# MicroPlayerSCH.net
KiCad netlist of a schematic drawn in Altium Designer
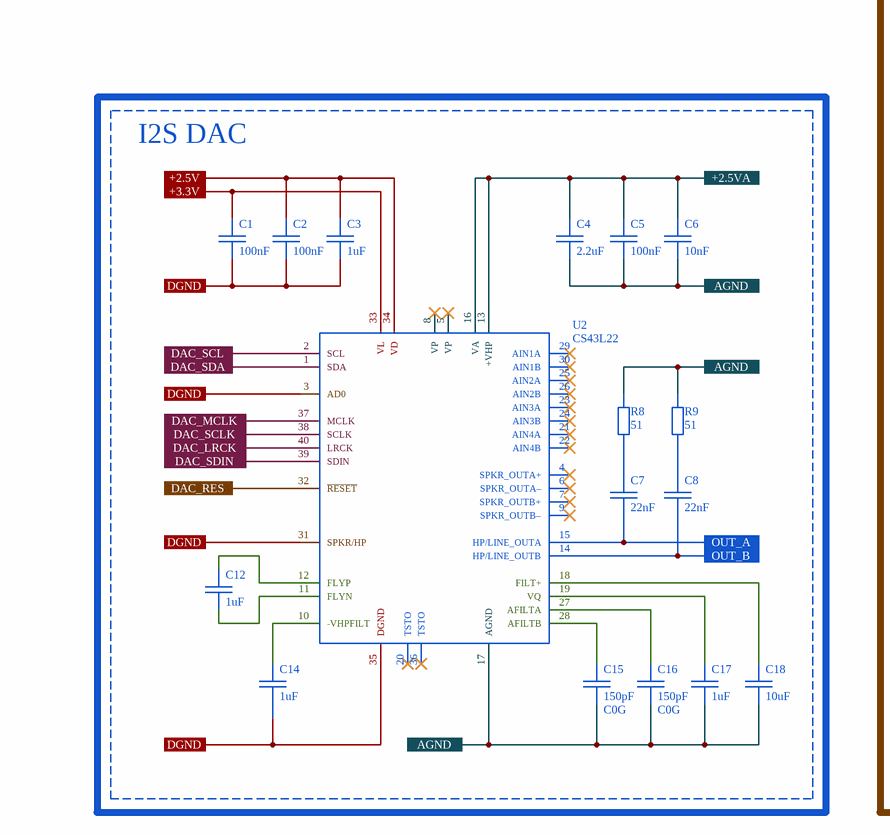
[diagram p0: MicroPlayerSCH.SchDoc, top left]
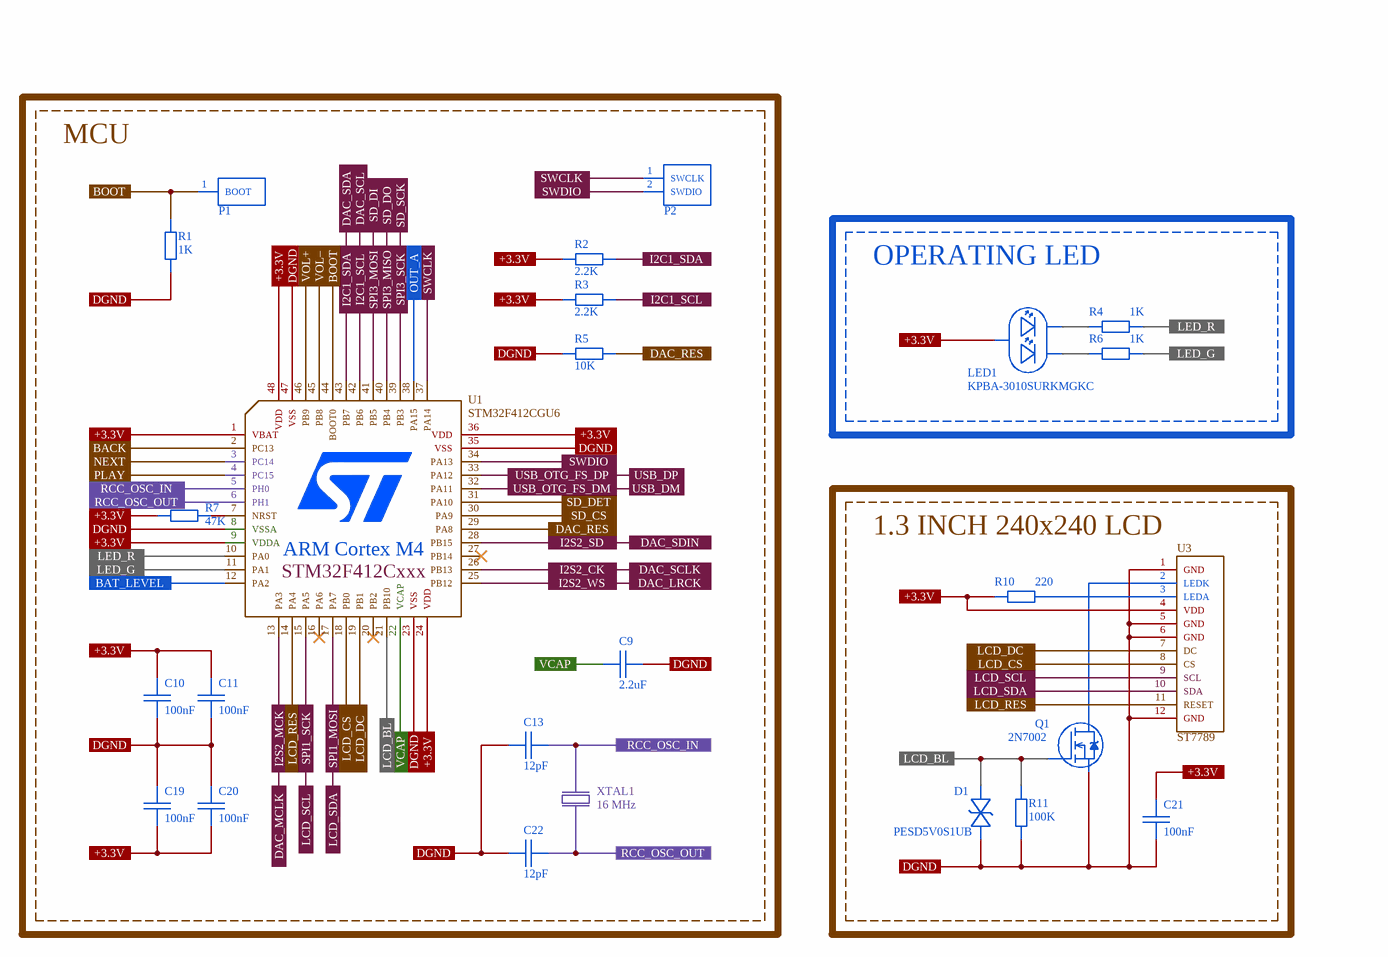
[diagram p1: MicroPlayerSCH.SchDoc, top right]
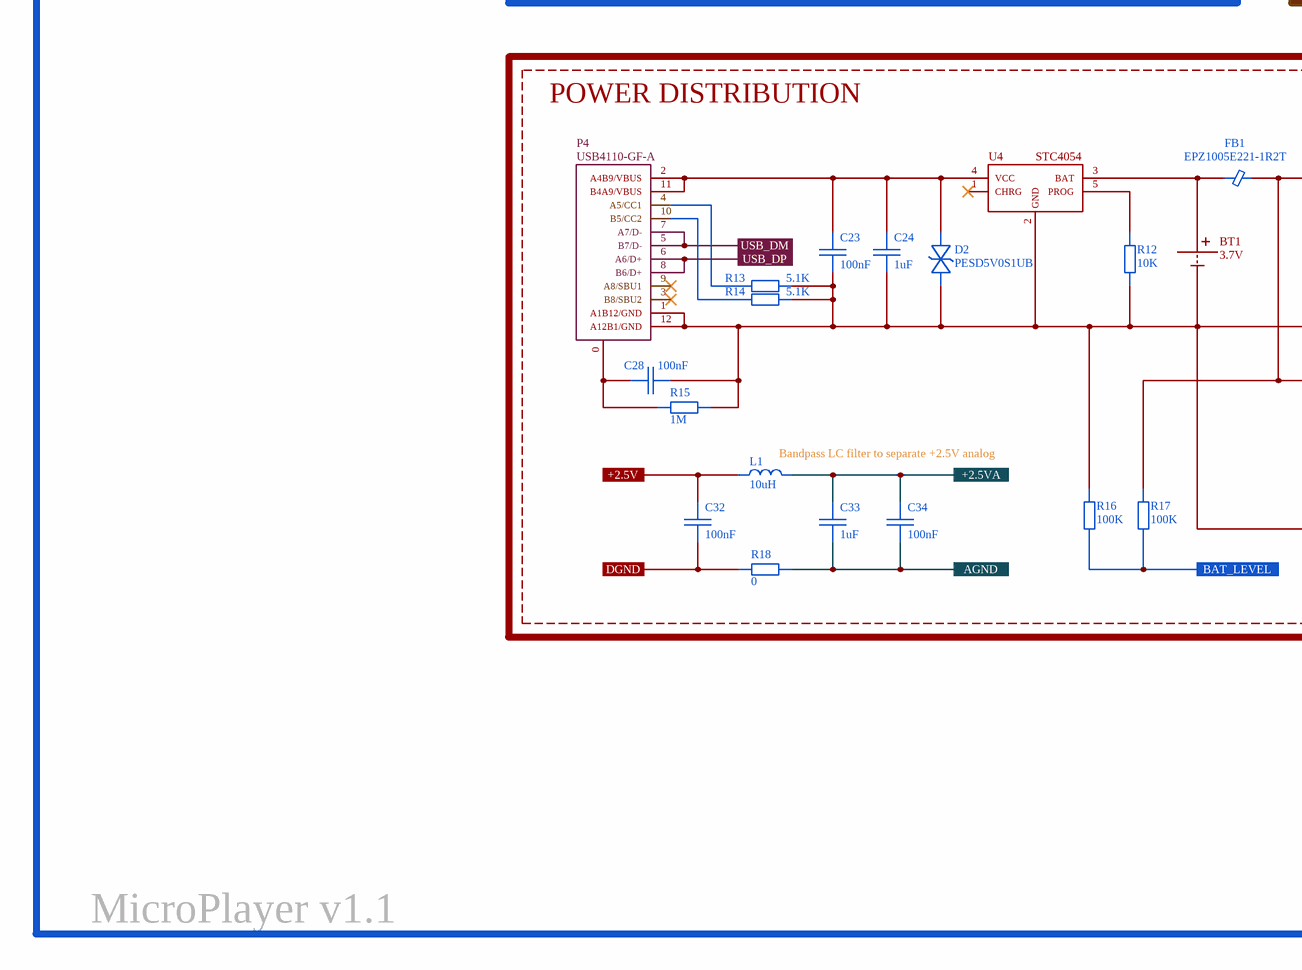
[diagram p2: MicroPlayerSCH.SchDoc, bottom left]
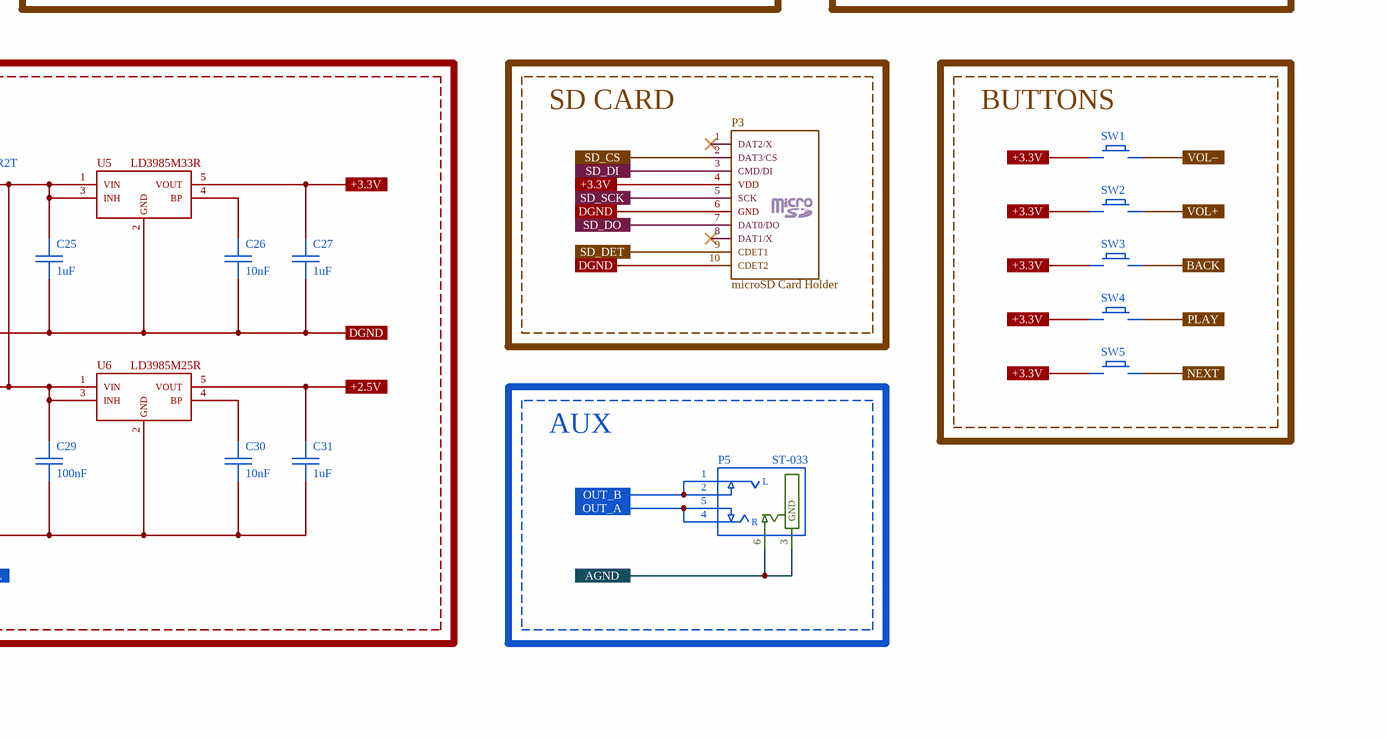
[diagram p3: MicroPlayerSCH.SchDoc, bottom right]

(export (version "E")
  (design (tool "Eeschema 10.0.6"))
  (components
    (comp (ref "BT1") (value "3.7V") (footprint "_2-PAD-SM") (libsource (lib "PowerUnits") (part "Battery")))
    (comp (ref "C1")
      (value "100nF")
      (footprint "C0402")
      (fields (field (name "VOLTAGE") "250V") (field (name "TOLERANCE") "5%"))
      (libsource (lib "CommonElements") (part "Cap"))
    )
    (comp (ref "C2")
      (value "100nF")
      (footprint "C0402")
      (fields (field (name "VOLTAGE") "250V") (field (name "TOLERANCE") "5%"))
      (libsource (lib "CommonElements") (part "Cap"))
    )
    (comp (ref "C3")
      (value "1uF")
      (footprint "C0402")
      (fields (field (name "VOLTAGE") "250V") (field (name "TOLERANCE") "5%"))
      (libsource (lib "CommonElements") (part "Cap"))
    )
    (comp (ref "C4")
      (value "2.2uF")
      (footprint "C0402")
      (fields (field (name "VOLTAGE") "250V") (field (name "TOLERANCE") "5%"))
      (libsource (lib "CommonElements") (part "Cap"))
    )
    (comp (ref "C5")
      (value "100nF")
      (footprint "C0402")
      (fields (field (name "VOLTAGE") "250V") (field (name "TOLERANCE") "5%"))
      (libsource (lib "CommonElements") (part "Cap"))
    )
    (comp (ref "C6")
      (value "10nF")
      (footprint "C0402")
      (fields (field (name "VOLTAGE") "250V") (field (name "TOLERANCE") "5%"))
      (libsource (lib "CommonElements") (part "Cap"))
    )
    (comp (ref "C7")
      (value "22nF")
      (footprint "C0402")
      (fields (field (name "VOLTAGE") "250V") (field (name "TOLERANCE") "5%"))
      (libsource (lib "CommonElements") (part "Cap"))
    )
    (comp (ref "C8")
      (value "22nF")
      (footprint "C0402")
      (fields (field (name "VOLTAGE") "250V") (field (name "TOLERANCE") "5%"))
      (libsource (lib "CommonElements") (part "Cap"))
    )
    (comp (ref "C9")
      (value "2.2uF")
      (footprint "C0402")
      (fields (field (name "VOLTAGE") "250V") (field (name "TOLERANCE") "5%"))
      (libsource (lib "CommonElements") (part "Cap"))
    )
    (comp (ref "C10")
      (value "100nF")
      (footprint "C0402")
      (fields (field (name "VOLTAGE") "250V") (field (name "TOLERANCE") "5%"))
      (libsource (lib "CommonElements") (part "Cap"))
    )
    (comp (ref "C11")
      (value "100nF")
      (footprint "C0402")
      (fields (field (name "VOLTAGE") "250V") (field (name "TOLERANCE") "5%"))
      (libsource (lib "CommonElements") (part "Cap"))
    )
    (comp (ref "C12")
      (value "1uF")
      (footprint "C0402")
      (fields (field (name "VOLTAGE") "250V") (field (name "TOLERANCE") "5%"))
      (libsource (lib "CommonElements") (part "Cap"))
    )
    (comp (ref "C13")
      (value "12pF")
      (footprint "C0402")
      (fields (field (name "VOLTAGE") "250V") (field (name "TOLERANCE") "5%"))
      (libsource (lib "CommonElements") (part "Cap"))
    )
    (comp (ref "C14")
      (value "1uF")
      (footprint "C0402")
      (fields (field (name "VOLTAGE") "250V") (field (name "TOLERANCE") "5%"))
      (libsource (lib "CommonElements") (part "Cap"))
    )
    (comp (ref "C15")
      (value "150pF")
      (footprint "C0402")
      (fields (field (name "VOLTAGE") "250V") (field (name "TOLERANCE") "5%") (field (name "NOTE") "C0G"))
      (libsource (lib "CommonElements") (part "Cap"))
    )
    (comp (ref "C16")
      (value "150pF")
      (footprint "C0402")
      (fields (field (name "VOLTAGE") "250V") (field (name "TOLERANCE") "5%") (field (name "NOTE") "C0G"))
      (libsource (lib "CommonElements") (part "Cap"))
    )
    (comp (ref "C17")
      (value "1uF")
      (footprint "C0402")
      (fields (field (name "VOLTAGE") "250V") (field (name "TOLERANCE") "5%"))
      (libsource (lib "CommonElements") (part "Cap"))
    )
    (comp (ref "C18")
      (value "10uF")
      (footprint "C0402")
      (fields (field (name "VOLTAGE") "250V") (field (name "TOLERANCE") "5%"))
      (libsource (lib "CommonElements") (part "Cap"))
    )
    (comp (ref "C19")
      (value "100nF")
      (footprint "C0402")
      (fields (field (name "VOLTAGE") "250V") (field (name "TOLERANCE") "5%"))
      (libsource (lib "CommonElements") (part "Cap"))
    )
    (comp (ref "C20")
      (value "100nF")
      (footprint "C0402")
      (fields (field (name "VOLTAGE") "250V") (field (name "TOLERANCE") "5%"))
      (libsource (lib "CommonElements") (part "Cap"))
    )
    (comp (ref "C21")
      (value "100nF")
      (footprint "C0402")
      (fields (field (name "VOLTAGE") "250V") (field (name "TOLERANCE") "5%"))
      (libsource (lib "CommonElements") (part "Cap"))
    )
    (comp (ref "C22")
      (value "12pF")
      (footprint "C0402")
      (fields (field (name "VOLTAGE") "250V") (field (name "TOLERANCE") "5%"))
      (libsource (lib "CommonElements") (part "Cap"))
    )
    (comp (ref "C23")
      (value "100nF")
      (footprint "C0402")
      (fields (field (name "VOLTAGE") "250V") (field (name "TOLERANCE") "5%"))
      (libsource (lib "CommonElements") (part "Cap"))
    )
    (comp (ref "C24")
      (value "1uF")
      (footprint "C0402")
      (fields (field (name "VOLTAGE") "250V") (field (name "TOLERANCE") "5%"))
      (libsource (lib "CommonElements") (part "Cap"))
    )
    (comp (ref "C25")
      (value "1uF")
      (footprint "C0402")
      (fields (field (name "VOLTAGE") "250V") (field (name "TOLERANCE") "5%"))
      (libsource (lib "CommonElements") (part "Cap"))
    )
    (comp (ref "C26")
      (value "10nF")
      (footprint "C0402")
      (fields (field (name "VOLTAGE") "250V") (field (name "TOLERANCE") "5%"))
      (libsource (lib "CommonElements") (part "Cap"))
    )
    (comp (ref "C27")
      (value "1uF")
      (footprint "C0402")
      (fields (field (name "VOLTAGE") "250V") (field (name "TOLERANCE") "5%"))
      (libsource (lib "CommonElements") (part "Cap"))
    )
    (comp (ref "C28")
      (value "100nF")
      (footprint "C0402")
      (fields (field (name "VOLTAGE") "250V") (field (name "TOLERANCE") "5%"))
      (libsource (lib "CommonElements") (part "Cap"))
    )
    (comp (ref "C29")
      (value "100nF")
      (footprint "C0402")
      (fields (field (name "VOLTAGE") "250V") (field (name "TOLERANCE") "5%"))
      (libsource (lib "CommonElements") (part "Cap"))
    )
    (comp (ref "C30")
      (value "10nF")
      (footprint "C0402")
      (fields (field (name "VOLTAGE") "250V") (field (name "TOLERANCE") "5%"))
      (libsource (lib "CommonElements") (part "Cap"))
    )
    (comp (ref "C31")
      (value "1uF")
      (footprint "C0402")
      (fields (field (name "VOLTAGE") "250V") (field (name "TOLERANCE") "5%"))
      (libsource (lib "CommonElements") (part "Cap"))
    )
    (comp (ref "C32")
      (value "100nF")
      (footprint "C0402")
      (fields (field (name "VOLTAGE") "250V") (field (name "TOLERANCE") "5%"))
      (libsource (lib "CommonElements") (part "Cap"))
    )
    (comp (ref "C33")
      (value "1uF")
      (footprint "C0402")
      (fields (field (name "VOLTAGE") "250V") (field (name "TOLERANCE") "5%"))
      (libsource (lib "CommonElements") (part "Cap"))
    )
    (comp (ref "C34")
      (value "100nF")
      (footprint "C0402")
      (fields (field (name "VOLTAGE") "250V") (field (name "TOLERANCE") "5%"))
      (libsource (lib "CommonElements") (part "Cap"))
    )
    (comp (ref "D1")
      (value "PESD5V0S1UB")
      (footprint "SOD-523")
      (libsource (lib "CommonElements") (part "Suppressor"))
    )
    (comp (ref "D2")
      (value "PESD5V0S1UB")
      (footprint "SOD-523")
      (libsource (lib "CommonElements") (part "Suppressor"))
    )
    (comp (ref "FB1")
      (value "EPZ1005E221-1R2T")
      (footprint "L0402")
      (libsource (lib "CommonElements") (part "Ferrite Bead"))
    )
    (comp (ref "L1")
      (value "10uH")
      (footprint "L0402")
      (fields (field (name "TOLERANCE") "30%") (field (name "PART NUMBER") "LQM21FN100N00K"))
      (libsource (lib "CommonElements") (part "Inductor"))
    )
    (comp (ref "LED1")
      (value "KPBA-3010SURKMGKC")
      (footprint "LED-3010")
      (libsource (lib "Miscellaneous") (part "LED-2C-CA"))
    )
    (comp (ref "P1") (value "P1") (footprint "_1-PAD-SM") (libsource (lib "Connectors") (part "P1")))
    (comp (ref "P2") (value "P2") (footprint "_2-PAD-SM") (libsource (lib "Connectors") (part "P2")))
    (comp (ref "P3")
      (value "microSD Card Holder")
      (footprint "SD-05")
      (libsource (lib "Connectors") (part "MicroSD-CD2"))
    )
    (comp (ref "P4")
      (value "USB4110-GF-A")
      (footprint "USB-TYPE-C")
      (libsource (lib "Connectors") (part "USB Type C with 0"))
    )
    (comp (ref "P5")
      (value "ST-033")
      (footprint "_3-PAD-TH")
      (libsource (lib "Connectors") (part "AJack Socket Stereo"))
    )
    (comp (ref "Q1")
      (value "2N7002")
      (footprint "SOT-23-3-312")
      (libsource (lib "CommonElements") (part "MOSFET-N"))
    )
    (comp (ref "R1")
      (value "1K")
      (footprint "R0402")
      (fields (field (name "TOLERANCE") "5%") (field (name "POWER") "0.125W"))
      (libsource (lib "CommonElements") (part "Res"))
    )
    (comp (ref "R2")
      (value "2.2K")
      (footprint "R0402")
      (fields (field (name "TOLERANCE") "5%") (field (name "POWER") "0.125W"))
      (libsource (lib "CommonElements") (part "Res"))
    )
    (comp (ref "R3")
      (value "2.2K")
      (footprint "R0402")
      (fields (field (name "TOLERANCE") "5%") (field (name "POWER") "0.125W"))
      (libsource (lib "CommonElements") (part "Res"))
    )
    (comp (ref "R4")
      (value "1K")
      (footprint "R0402")
      (fields (field (name "TOLERANCE") "5%") (field (name "POWER") "0.125W"))
      (libsource (lib "CommonElements") (part "Res"))
    )
    (comp (ref "R5")
      (value "10K")
      (footprint "R0402")
      (fields (field (name "TOLERANCE") "5%") (field (name "POWER") "0.125W"))
      (libsource (lib "CommonElements") (part "Res"))
    )
    (comp (ref "R6")
      (value "1K")
      (footprint "R0402")
      (fields (field (name "TOLERANCE") "5%") (field (name "POWER") "0.125W"))
      (libsource (lib "CommonElements") (part "Res"))
    )
    (comp (ref "R7")
      (value "47K")
      (footprint "R0402")
      (fields (field (name "TOLERANCE") "5%") (field (name "POWER") "0.125W"))
      (libsource (lib "CommonElements") (part "Res"))
    )
    (comp (ref "R8")
      (value "51")
      (footprint "R0402")
      (fields (field (name "TOLERANCE") "5%") (field (name "POWER") "0.125W"))
      (libsource (lib "CommonElements") (part "Res"))
    )
    (comp (ref "R9")
      (value "51")
      (footprint "R0402")
      (fields (field (name "TOLERANCE") "5%") (field (name "POWER") "0.125W"))
      (libsource (lib "CommonElements") (part "Res"))
    )
    (comp (ref "R10")
      (value "220")
      (footprint "R0402")
      (fields (field (name "TOLERANCE") "5%") (field (name "POWER") "0.125W"))
      (libsource (lib "CommonElements") (part "Res"))
    )
    (comp (ref "R11")
      (value "100K")
      (footprint "R0402")
      (fields (field (name "TOLERANCE") "5%") (field (name "POWER") "0.125W"))
      (libsource (lib "CommonElements") (part "Res"))
    )
    (comp (ref "R12")
      (value "10K")
      (footprint "R0402")
      (fields (field (name "TOLERANCE") "5%") (field (name "POWER") "0.125W"))
      (libsource (lib "CommonElements") (part "Res"))
    )
    (comp (ref "R13")
      (value "5.1K")
      (footprint "R0402")
      (fields (field (name "TOLERANCE") "5%") (field (name "POWER") "0.125W"))
      (libsource (lib "CommonElements") (part "Res"))
    )
    (comp (ref "R14")
      (value "5.1K")
      (footprint "R0402")
      (fields (field (name "TOLERANCE") "5%") (field (name "POWER") "0.125W"))
      (libsource (lib "CommonElements") (part "Res"))
    )
    (comp (ref "R15")
      (value "1M")
      (footprint "R0402")
      (fields (field (name "TOLERANCE") "5%") (field (name "POWER") "0.125W"))
      (libsource (lib "CommonElements") (part "Res"))
    )
    (comp (ref "R16")
      (value "100K")
      (footprint "R0402")
      (fields (field (name "TOLERANCE") "5%") (field (name "POWER") "0.125W"))
      (libsource (lib "CommonElements") (part "Res"))
    )
    (comp (ref "R17")
      (value "100K")
      (footprint "R0402")
      (fields (field (name "TOLERANCE") "5%") (field (name "POWER") "0.125W"))
      (libsource (lib "CommonElements") (part "Res"))
    )
    (comp (ref "R18")
      (value "0")
      (footprint "R0402")
      (fields (field (name "TOLERANCE") "5%") (field (name "POWER") "0.125W"))
      (libsource (lib "CommonElements") (part "Res"))
    )
    (comp (ref "SW1")
      (value "~")
      (footprint "BUT-SMD-4X3.5X2MM")
      (libsource (lib "CommonElements") (part "Button"))
    )
    (comp (ref "SW2")
      (value "~")
      (footprint "BUT-SMD-4X3.5X2MM")
      (libsource (lib "CommonElements") (part "Button"))
    )
    (comp (ref "SW3")
      (value "~")
      (footprint "BUT-SMD-4X3.5X2MM")
      (libsource (lib "CommonElements") (part "Button"))
    )
    (comp (ref "SW4")
      (value "~")
      (footprint "BUT-SMD-4X3.5X2MM")
      (libsource (lib "CommonElements") (part "Button"))
    )
    (comp (ref "SW5")
      (value "~")
      (footprint "BUT-SMD-4X3.5X2MM")
      (libsource (lib "CommonElements") (part "Button"))
    )
    (comp (ref "U1")
      (value "STM32F412CGU6")
      (footprint "UFQFPN48")
      (libsource (lib "STM32") (part "STM32F412Cxxx"))
    )
    (comp (ref "U2")
      (value "CS43L22")
      (footprint "QFN40")
      (description "Low Power, Stereo DAC w/Headphone & Speaker Amps")
      (libsource (lib "Miscellaneous") (part "CS43L22"))
    )
    (comp (ref "U3")
      (value "ST7789")
      (footprint "1.3INCH_LCD_WELDED")
      (description "135x240 Display")
      (libsource (lib "Modules") (part "1.3inch TFT LCD 12-pin"))
    )
    (comp (ref "U4")
      (value "STC4054")
      (footprint "SOT-23-5")
      (description "800mA Standalone linear Li-Ion Battery charger with thermal regulation")
      (libsource (lib "PowerUnits") (part "STC4054"))
    )
    (comp (ref "U5")
      (value "LD3985M33R")
      (footprint "SOT-23-5")
      (description "Ultra low drop and low noise BiCMOS voltage regulators, 150 mA")
      (libsource (lib "PowerUnits") (part "LD3985"))
    )
    (comp (ref "U6")
      (value "LD3985M25R")
      (footprint "SOT-23-5")
      (description "Ultra low drop and low noise BiCMOS voltage regulators, 150 mA")
      (libsource (lib "PowerUnits") (part "LD3985"))
    )
    (comp (ref "XTAL1")
      (value "16 MHz")
      (footprint "7U")
      (fields (field (name "TOLERANCE") "0.001%"))
      (libsource (lib "CommonElements") (part "Crystal"))
    )
  )
  (nets
    (net (code "1") (name "/+2.5V") (class "Default")
      (node (ref "C2") (pin "2") (pintype "passive"))
      (node (ref "C3") (pin "2") (pintype "passive"))
      (node (ref "C31") (pin "2") (pintype "passive"))
      (node (ref "C32") (pin "1") (pintype "passive"))
      (node (ref "L1") (pin "1") (pintype "passive"))
      (node (ref "U2") (pin "34") (pinfunction "VD_34") (pintype "passive"))
      (node (ref "U6") (pin "5") (pinfunction "VOUT_5") (pintype "passive"))
    )
    (net (code "2") (name "/+2.5VA") (class "Default")
      (node (ref "C33") (pin "1") (pintype "passive"))
      (node (ref "C34") (pin "1") (pintype "passive"))
      (node (ref "C4") (pin "2") (pintype "passive"))
      (node (ref "C5") (pin "2") (pintype "passive"))
      (node (ref "C6") (pin "2") (pintype "passive"))
      (node (ref "L1") (pin "2") (pintype "passive"))
      (node (ref "U2") (pin "13") (pinfunction "+VHP_13") (pintype "passive"))
      (node (ref "U2") (pin "16") (pinfunction "VA_16") (pintype "passive"))
    )
    (net (code "3") (name "/+3.3V") (class "Default")
      (node (ref "C1") (pin "2") (pintype "passive"))
      (node (ref "C10") (pin "2") (pintype "passive"))
      (node (ref "C11") (pin "2") (pintype "passive"))
      (node (ref "C19") (pin "1") (pintype "passive"))
      (node (ref "C20") (pin "1") (pintype "passive"))
      (node (ref "C21") (pin "2") (pintype "passive"))
      (node (ref "C27") (pin "2") (pintype "passive"))
      (node (ref "LED1") (pin "1") (pintype "passive"))
      (node (ref "P3") (pin "4") (pinfunction "VDD_4") (pintype "passive"))
      (node (ref "R10") (pin "1") (pintype "passive"))
      (node (ref "R2") (pin "1") (pintype "passive"))
      (node (ref "R3") (pin "1") (pintype "passive"))
      (node (ref "R7") (pin "1") (pintype "passive"))
      (node (ref "SW1") (pin "1") (pintype "passive"))
      (node (ref "SW2") (pin "1") (pintype "passive"))
      (node (ref "SW3") (pin "1") (pintype "passive"))
      (node (ref "SW4") (pin "1") (pintype "passive"))
      (node (ref "SW5") (pin "1") (pintype "passive"))
      (node (ref "U1") (pin "1") (pinfunction "VBAT_1") (pintype "passive"))
      (node (ref "U1") (pin "24") (pinfunction "VDD_24") (pintype "passive"))
      (node (ref "U1") (pin "36") (pinfunction "VDD_36") (pintype "passive"))
      (node (ref "U1") (pin "48") (pinfunction "VDD_48") (pintype "passive"))
      (node (ref "U1") (pin "9") (pinfunction "VDDA_9") (pintype "passive"))
      (node (ref "U2") (pin "33") (pinfunction "VL_33") (pintype "passive"))
      (node (ref "U3") (pin "4") (pinfunction "VDD_4") (pintype "passive"))
      (node (ref "U5") (pin "5") (pinfunction "VOUT_5") (pintype "passive"))
    )
    (net (code "4") (name "/AGND") (class "Default")
      (node (ref "C15") (pin "1") (pintype "passive"))
      (node (ref "C16") (pin "1") (pintype "passive"))
      (node (ref "C17") (pin "2") (pintype "passive"))
      (node (ref "C18") (pin "2") (pintype "passive"))
      (node (ref "C33") (pin "2") (pintype "passive"))
      (node (ref "C34") (pin "2") (pintype "passive"))
      (node (ref "C4") (pin "1") (pintype "passive"))
      (node (ref "C5") (pin "1") (pintype "passive"))
      (node (ref "C6") (pin "1") (pintype "passive"))
      (node (ref "P5") (pin "3") (pinfunction "GND_3") (pintype "passive"))
      (node (ref "P5") (pin "6") (pintype "passive"))
      (node (ref "R18") (pin "2") (pintype "passive"))
      (node (ref "R8") (pin "2") (pintype "passive"))
      (node (ref "R9") (pin "2") (pintype "passive"))
      (node (ref "U2") (pin "17") (pinfunction "AGND_17") (pintype "passive"))
    )
    (net (code "5") (name "/BACK") (class "Default")
      (node (ref "SW3") (pin "2") (pintype "passive"))
      (node (ref "U1") (pin "2") (pinfunction "PC13_2") (pintype "passive"))
    )
    (net (code "6") (name "/BAT_LEVEL") (class "Default")
      (node (ref "R16") (pin "1") (pintype "passive"))
      (node (ref "R17") (pin "1") (pintype "passive"))
      (node (ref "U1") (pin "12") (pinfunction "PA2_12") (pintype "passive"))
    )
    (net (code "7") (name "/BOOT") (class "Default")
      (node (ref "P1") (pin "1") (pinfunction "BOOT_1") (pintype "passive"))
      (node (ref "R1") (pin "1") (pintype "passive"))
      (node (ref "U1") (pin "44") (pinfunction "BOOT0_44") (pintype "passive"))
    )
    (net (code "8") (name "/DAC_LRCK") (class "Default")
      (node (ref "U1") (pin "25") (pinfunction "PB12_25") (pintype "passive"))
      (node (ref "U2") (pin "40") (pinfunction "LRCK_40") (pintype "passive"))
    )
    (net (code "9") (name "/DAC_MCLK") (class "Default")
      (node (ref "U1") (pin "13") (pinfunction "PA3_13") (pintype "passive"))
      (node (ref "U2") (pin "37") (pinfunction "MCLK_37") (pintype "passive"))
    )
    (net (code "10") (name "/DAC_RES") (class "Default")
      (node (ref "R5") (pin "2") (pintype "passive"))
      (node (ref "U1") (pin "29") (pinfunction "PA8_29") (pintype "passive"))
      (node (ref "U2") (pin "32") (pinfunction "RESET_32") (pintype "passive"))
    )
    (net (code "11") (name "/DAC_SCL") (class "Default")
      (node (ref "R3") (pin "2") (pintype "passive"))
      (node (ref "U1") (pin "42") (pinfunction "PB6_42") (pintype "passive"))
      (node (ref "U2") (pin "2") (pinfunction "SCL_2") (pintype "passive"))
    )
    (net (code "12") (name "/DAC_SCLK") (class "Default")
      (node (ref "U1") (pin "26") (pinfunction "PB13_26") (pintype "passive"))
      (node (ref "U2") (pin "38") (pinfunction "SCLK_38") (pintype "passive"))
    )
    (net (code "13") (name "/DAC_SDA") (class "Default")
      (node (ref "R2") (pin "2") (pintype "passive"))
      (node (ref "U1") (pin "43") (pinfunction "PB7_43") (pintype "passive"))
      (node (ref "U2") (pin "1") (pinfunction "SDA_1") (pintype "passive"))
    )
    (net (code "14") (name "/DAC_SDIN") (class "Default")
      (node (ref "U1") (pin "28") (pinfunction "PB15_28") (pintype "passive"))
      (node (ref "U2") (pin "39") (pinfunction "SDIN_39") (pintype "passive"))
    )
    (net (code "15") (name "/DGND") (class "Default")
      (node (ref "BT1") (pin "2") (pintype "passive"))
      (node (ref "C1") (pin "1") (pintype "passive"))
      (node (ref "C10") (pin "1") (pintype "passive"))
      (node (ref "C11") (pin "1") (pintype "passive"))
      (node (ref "C13") (pin "2") (pintype "passive"))
      (node (ref "C14") (pin "1") (pintype "passive"))
      (node (ref "C19") (pin "2") (pintype "passive"))
      (node (ref "C2") (pin "1") (pintype "passive"))
      (node (ref "C20") (pin "2") (pintype "passive"))
      (node (ref "C21") (pin "1") (pintype "passive"))
      (node (ref "C22") (pin "2") (pintype "passive"))
      (node (ref "C23") (pin "1") (pintype "passive"))
      (node (ref "C24") (pin "2") (pintype "passive"))
      (node (ref "C25") (pin "1") (pintype "passive"))
      (node (ref "C26") (pin "1") (pintype "passive"))
      (node (ref "C27") (pin "1") (pintype "passive"))
      (node (ref "C28") (pin "1") (pintype "passive"))
      (node (ref "C29") (pin "1") (pintype "passive"))
      (node (ref "C3") (pin "1") (pintype "passive"))
      (node (ref "C30") (pin "1") (pintype "passive"))
      (node (ref "C31") (pin "1") (pintype "passive"))
      (node (ref "C32") (pin "2") (pintype "passive"))
      (node (ref "C9") (pin "2") (pintype "passive"))
      (node (ref "D1") (pin "1") (pintype "passive"))
      (node (ref "D2") (pin "1") (pintype "passive"))
      (node (ref "P3") (pin "10") (pinfunction "CDET2_10") (pintype "passive"))
      (node (ref "P3") (pin "6") (pinfunction "GND_6") (pintype "passive"))
      (node (ref "P4") (pin "1") (pinfunction "A1B12/GND_1") (pintype "passive"))
      (node (ref "P4") (pin "12") (pinfunction "A12B1/GND_12") (pintype "passive"))
      (node (ref "Q1") (pin "2") (pinfunction "S_2") (pintype "passive"))
      (node (ref "R1") (pin "2") (pintype "passive"))
      (node (ref "R11") (pin "1") (pintype "passive"))
      (node (ref "R12") (pin "1") (pintype "passive"))
      (node (ref "R13") (pin "1") (pintype "passive"))
      (node (ref "R14") (pin "1") (pintype "passive"))
      (node (ref "R15") (pin "1") (pintype "passive"))
      (node (ref "R16") (pin "2") (pintype "passive"))
      (node (ref "R18") (pin "1") (pintype "passive"))
      (node (ref "R5") (pin "1") (pintype "passive"))
      (node (ref "U1") (pin "23") (pinfunction "VSS_23") (pintype "passive"))
      (node (ref "U1") (pin "35") (pinfunction "VSS_35") (pintype "passive"))
      (node (ref "U1") (pin "47") (pinfunction "VSS_47") (pintype "passive"))
      (node (ref "U1") (pin "8") (pinfunction "VSSA_8") (pintype "passive"))
      (node (ref "U2") (pin "3") (pinfunction "AD0_3") (pintype "passive"))
      (node (ref "U2") (pin "31") (pinfunction "SPKR/HP_31") (pintype "passive"))
      (node (ref "U2") (pin "35") (pinfunction "DGND_35") (pintype "passive"))
      (node (ref "U3") (pin "1") (pinfunction "GND_1") (pintype "passive"))
      (node (ref "U3") (pin "12") (pinfunction "GND_12") (pintype "passive"))
      (node (ref "U3") (pin "5") (pinfunction "GND_5") (pintype "passive"))
      (node (ref "U3") (pin "6") (pinfunction "GND_6") (pintype "passive"))
      (node (ref "U4") (pin "2") (pinfunction "GND_2") (pintype "passive"))
      (node (ref "U5") (pin "2") (pinfunction "GND_2") (pintype "passive"))
      (node (ref "U6") (pin "2") (pinfunction "GND_2") (pintype "passive"))
    )
    (net (code "16") (name "/LCD_BL") (class "Default")
      (node (ref "D1") (pin "2") (pintype "passive"))
      (node (ref "Q1") (pin "1") (pinfunction "G_1") (pintype "passive"))
      (node (ref "R11") (pin "2") (pintype "passive"))
      (node (ref "U1") (pin "21") (pinfunction "PB10_21") (pintype "passive"))
    )
    (net (code "17") (name "/LCD_CS") (class "Default")
      (node (ref "U1") (pin "18") (pinfunction "PB0_18") (pintype "passive"))
      (node (ref "U3") (pin "8") (pinfunction "CS_8") (pintype "passive"))
    )
    (net (code "18") (name "/LCD_DC") (class "Default")
      (node (ref "U1") (pin "19") (pinfunction "PB1_19") (pintype "passive"))
      (node (ref "U3") (pin "7") (pinfunction "DC_7") (pintype "passive"))
    )
    (net (code "19") (name "/LCD_RES") (class "Default")
      (node (ref "U1") (pin "14") (pinfunction "PA4_14") (pintype "passive"))
      (node (ref "U3") (pin "11") (pinfunction "RESET_11") (pintype "passive"))
    )
    (net (code "20") (name "/LCD_SCL") (class "Default")
      (node (ref "U1") (pin "15") (pinfunction "PA5_15") (pintype "passive"))
      (node (ref "U3") (pin "9") (pinfunction "SCL_9") (pintype "passive"))
    )
    (net (code "21") (name "/LCD_SDA") (class "Default")
      (node (ref "U1") (pin "17") (pinfunction "PA7_17") (pintype "passive"))
      (node (ref "U3") (pin "10") (pinfunction "SDA_10") (pintype "passive"))
    )
    (net (code "22") (name "/LED_G") (class "Default")
      (node (ref "R6") (pin "1") (pintype "passive"))
      (node (ref "U1") (pin "11") (pinfunction "PA1_11") (pintype "passive"))
    )
    (net (code "23") (name "/LED_R") (class "Default")
      (node (ref "R4") (pin "2") (pintype "passive"))
      (node (ref "U1") (pin "10") (pinfunction "PA0_10") (pintype "passive"))
    )
    (net (code "24") (name "/NEXT") (class "Default")
      (node (ref "SW5") (pin "2") (pintype "passive"))
      (node (ref "U1") (pin "3") (pinfunction "PC14_3") (pintype "passive"))
    )
    (net (code "25") (name "/OUT_A") (class "Default")
      (node (ref "C7") (pin "1") (pintype "passive"))
      (node (ref "P5") (pin "4") (pinfunction "R_4") (pintype "passive"))
      (node (ref "P5") (pin "5") (pintype "passive"))
      (node (ref "U1") (pin "38") (pinfunction "PA15_38") (pintype "passive"))
      (node (ref "U2") (pin "15") (pinfunction "HP/LINE_OUTA_15") (pintype "passive"))
    )
    (net (code "26") (name "/OUT_B") (class "Default")
      (node (ref "C8") (pin "1") (pintype "passive"))
      (node (ref "P5") (pin "1") (pinfunction "L_1") (pintype "passive"))
      (node (ref "P5") (pin "2") (pintype "passive"))
      (node (ref "U2") (pin "14") (pinfunction "HP/LINE_OUTB_14") (pintype "passive"))
    )
    (net (code "27") (name "/PLAY") (class "Default")
      (node (ref "SW4") (pin "2") (pintype "passive"))
      (node (ref "U1") (pin "4") (pinfunction "PC15_4") (pintype "passive"))
    )
    (net (code "28") (name "/RCC_OSC_IN") (class "Default")
      (node (ref "C13") (pin "1") (pintype "passive"))
      (node (ref "U1") (pin "5") (pinfunction "PH0_5") (pintype "passive"))
      (node (ref "XTAL1") (pin "1") (pintype "passive"))
    )
    (net (code "29") (name "/RCC_OSC_OUT") (class "Default")
      (node (ref "C22") (pin "1") (pintype "passive"))
      (node (ref "U1") (pin "6") (pinfunction "PH1_6") (pintype "passive"))
      (node (ref "XTAL1") (pin "2") (pintype "passive"))
    )
    (net (code "30") (name "/SD_CS") (class "Default")
      (node (ref "P3") (pin "2") (pinfunction "DAT3/CS_2") (pintype "passive"))
      (node (ref "U1") (pin "30") (pinfunction "PA9_30") (pintype "passive"))
    )
    (net (code "31") (name "/SD_DET") (class "Default")
      (node (ref "P3") (pin "9") (pinfunction "CDET1_9") (pintype "passive"))
      (node (ref "U1") (pin "31") (pinfunction "PA10_31") (pintype "passive"))
    )
    (net (code "32") (name "/SD_DI") (class "Default")
      (node (ref "P3") (pin "3") (pinfunction "CMD/DI_3") (pintype "passive"))
      (node (ref "U1") (pin "41") (pinfunction "PB5_41") (pintype "passive"))
    )
    (net (code "33") (name "/SD_DO") (class "Default")
      (node (ref "P3") (pin "7") (pinfunction "DAT0/DO_7") (pintype "passive"))
      (node (ref "U1") (pin "40") (pinfunction "PB4_40") (pintype "passive"))
    )
    (net (code "34") (name "/SD_SCK") (class "Default")
      (node (ref "P3") (pin "5") (pinfunction "SCK_5") (pintype "passive"))
      (node (ref "U1") (pin "39") (pinfunction "PB3_39") (pintype "passive"))
    )
    (net (code "35") (name "/SWCLK") (class "Default")
      (node (ref "P2") (pin "1") (pinfunction "SWCLK_1") (pintype "passive"))
      (node (ref "U1") (pin "37") (pinfunction "PA14_37") (pintype "passive"))
    )
    (net (code "36") (name "/SWDIO") (class "Default")
      (node (ref "P2") (pin "2") (pinfunction "SWDIO_2") (pintype "passive"))
      (node (ref "U1") (pin "34") (pinfunction "PA13_34") (pintype "passive"))
    )
    (net (code "37") (name "/USB_DM") (class "Default")
      (node (ref "P4") (pin "5") (pinfunction "B7/D-_5") (pintype "passive"))
      (node (ref "P4") (pin "7") (pinfunction "A7/D-_7") (pintype "passive"))
      (node (ref "U1") (pin "32") (pinfunction "PA11_32") (pintype "passive"))
    )
    (net (code "38") (name "/USB_DP") (class "Default")
      (node (ref "P4") (pin "6") (pinfunction "A6/D+_6") (pintype "passive"))
      (node (ref "P4") (pin "8") (pinfunction "B6/D+_8") (pintype "passive"))
      (node (ref "U1") (pin "33") (pinfunction "PA12_33") (pintype "passive"))
    )
    (net (code "39") (name "/VCAP") (class "Default")
      (node (ref "C9") (pin "1") (pintype "passive"))
      (node (ref "U1") (pin "22") (pinfunction "VCAP_22") (pintype "passive"))
    )
    (net (code "40") (name "/VOL+") (class "Default")
      (node (ref "SW2") (pin "2") (pintype "passive"))
      (node (ref "U1") (pin "46") (pinfunction "PB9_46") (pintype "passive"))
    )
    (net (code "41") (name "/VOL–") (class "Default")
      (node (ref "SW1") (pin "2") (pintype "passive"))
      (node (ref "U1") (pin "45") (pinfunction "PB8_45") (pintype "passive"))
    )
    (net (code "42") (name "Net-(C7-Pad2)") (class "Default")
      (node (ref "C7") (pin "2") (pintype "passive"))
      (node (ref "R8") (pin "1") (pintype "passive"))
    )
    (net (code "43") (name "Net-(C8-Pad2)") (class "Default")
      (node (ref "C8") (pin "2") (pintype "passive"))
      (node (ref "R9") (pin "1") (pintype "passive"))
    )
    (net (code "44") (name "Net-(C28-Pad2)") (class "Default")
      (node (ref "C28") (pin "2") (pintype "passive"))
      (node (ref "P4") (pin "0") (pintype "passive"))
      (node (ref "R15") (pin "2") (pintype "passive"))
    )
    (net (code "45") (name "Net-(LED1-Pad2)") (class "Default")
      (node (ref "LED1") (pin "2") (pintype "passive"))
      (node (ref "R4") (pin "1") (pintype "passive"))
    )
    (net (code "46") (name "Net-(LED1-Pad3)") (class "Default")
      (node (ref "LED1") (pin "3") (pintype "passive"))
      (node (ref "R6") (pin "2") (pintype "passive"))
    )
    (net (code "47") (name "Net-(P4-A4B9{slash}VBUS)") (class "Default")
      (node (ref "C23") (pin "2") (pintype "passive"))
      (node (ref "C24") (pin "1") (pintype "passive"))
      (node (ref "D2") (pin "2") (pintype "passive"))
      (node (ref "P4") (pin "11") (pinfunction "B4A9/VBUS_11") (pintype "passive"))
      (node (ref "P4") (pin "2") (pinfunction "A4B9/VBUS_2") (pintype "passive"))
      (node (ref "U4") (pin "4") (pinfunction "VCC_4") (pintype "passive"))
    )
    (net (code "48") (name "Net-(P4-A5{slash}CC1)") (class "Default")
      (node (ref "P4") (pin "4") (pinfunction "A5/CC1_4") (pintype "passive"))
      (node (ref "R13") (pin "2") (pintype "passive"))
    )
    (net (code "49") (name "Net-(P4-B5{slash}CC2)") (class "Default")
      (node (ref "P4") (pin "10") (pinfunction "B5/CC2_10") (pintype "passive"))
      (node (ref "R14") (pin "2") (pintype "passive"))
    )
    (net (code "50") (name "Net-(Q1-D)") (class "Default")
      (node (ref "Q1") (pin "3") (pinfunction "D_3") (pintype "passive"))
      (node (ref "U3") (pin "2") (pinfunction "LEDK_2") (pintype "passive"))
    )
    (net (code "51") (name "Net-(U1-NRST)") (class "Default")
      (node (ref "R7") (pin "2") (pintype "passive"))
      (node (ref "U1") (pin "7") (pinfunction "NRST_7") (pintype "passive"))
    )
    (net (code "52") (name "Net-(U2--VHPFILT)") (class "Default")
      (node (ref "C14") (pin "2") (pintype "passive"))
      (node (ref "U2") (pin "10") (pinfunction "-VHPFILT_10") (pintype "passive"))
    )
    (net (code "53") (name "Net-(U2-AFILTA)") (class "Default")
      (node (ref "C16") (pin "2") (pintype "passive"))
      (node (ref "U2") (pin "27") (pinfunction "AFILTA_27") (pintype "passive"))
    )
    (net (code "54") (name "Net-(U2-AFILTB)") (class "Default")
      (node (ref "C15") (pin "2") (pintype "passive"))
      (node (ref "U2") (pin "28") (pinfunction "AFILTB_28") (pintype "passive"))
    )
    (net (code "55") (name "Net-(U2-FILT+)") (class "Default")
      (node (ref "C18") (pin "1") (pintype "passive"))
      (node (ref "U2") (pin "18") (pinfunction "FILT+_18") (pintype "passive"))
    )
    (net (code "56") (name "Net-(U2-FLYN)") (class "Default")
      (node (ref "C12") (pin "1") (pintype "passive"))
      (node (ref "U2") (pin "11") (pinfunction "FLYN_11") (pintype "passive"))
    )
    (net (code "57") (name "Net-(U2-FLYP)") (class "Default")
      (node (ref "C12") (pin "2") (pintype "passive"))
      (node (ref "U2") (pin "12") (pinfunction "FLYP_12") (pintype "passive"))
    )
    (net (code "58") (name "Net-(U2-VQ)") (class "Default")
      (node (ref "C17") (pin "1") (pintype "passive"))
      (node (ref "U2") (pin "19") (pinfunction "VQ_19") (pintype "passive"))
    )
    (net (code "59") (name "Net-(U3-LEDA)") (class "Default")
      (node (ref "R10") (pin "2") (pintype "passive"))
      (node (ref "U3") (pin "3") (pinfunction "LEDA_3") (pintype "passive"))
    )
    (net (code "60") (name "Net-(U4-BAT)") (class "Default")
      (node (ref "BT1") (pin "1") (pintype "passive"))
      (node (ref "FB1") (pin "1") (pintype "passive"))
      (node (ref "U4") (pin "3") (pinfunction "BAT_3") (pintype "passive"))
    )
    (net (code "61") (name "Net-(U4-PROG)") (class "Default")
      (node (ref "R12") (pin "2") (pintype "passive"))
      (node (ref "U4") (pin "5") (pinfunction "PROG_5") (pintype "passive"))
    )
    (net (code "62") (name "Net-(U5-BP)") (class "Default")
      (node (ref "C26") (pin "2") (pintype "passive"))
      (node (ref "U5") (pin "4") (pinfunction "BP_4") (pintype "passive"))
    )
    (net (code "63") (name "Net-(U5-INH)") (class "Default")
      (node (ref "C25") (pin "2") (pintype "passive"))
      (node (ref "C29") (pin "2") (pintype "passive"))
      (node (ref "FB1") (pin "2") (pintype "passive"))
      (node (ref "R17") (pin "2") (pintype "passive"))
      (node (ref "U5") (pin "1") (pinfunction "VIN_1") (pintype "passive"))
      (node (ref "U5") (pin "3") (pinfunction "INH_3") (pintype "passive"))
      (node (ref "U6") (pin "1") (pinfunction "VIN_1") (pintype "passive"))
      (node (ref "U6") (pin "3") (pinfunction "INH_3") (pintype "passive"))
    )
    (net (code "64") (name "Net-(U6-BP)") (class "Default")
      (node (ref "C30") (pin "2") (pintype "passive"))
      (node (ref "U6") (pin "4") (pinfunction "BP_4") (pintype "passive"))
    )
    (net (code "65") (name "unconnected-(P3-DAT1{slash}X-Pad8)") (class "Default")
      (node (ref "P3") (pin "8") (pinfunction "DAT1/X_8") (pintype "passive+no_connect"))
    )
    (net (code "66") (name "unconnected-(P3-DAT2{slash}X-Pad1)") (class "Default")
      (node (ref "P3") (pin "1") (pinfunction "DAT2/X_1") (pintype "passive+no_connect"))
    )
    (net (code "67") (name "unconnected-(P4-A8{slash}SBU1-Pad9)") (class "Default")
      (node (ref "P4") (pin "9") (pinfunction "A8/SBU1_9") (pintype "passive+no_connect"))
    )
    (net (code "68") (name "unconnected-(P4-B8{slash}SBU2-Pad3)") (class "Default")
      (node (ref "P4") (pin "3") (pinfunction "B8/SBU2_3") (pintype "passive+no_connect"))
    )
    (net (code "69") (name "unconnected-(U1-PA6-Pad16)") (class "Default")
      (node (ref "U1") (pin "16") (pinfunction "PA6_16") (pintype "passive+no_connect"))
    )
    (net (code "70") (name "unconnected-(U1-PB2-Pad20)") (class "Default")
      (node (ref "U1") (pin "20") (pinfunction "PB2_20") (pintype "passive+no_connect"))
    )
    (net (code "71") (name "unconnected-(U1-PB14-Pad27)") (class "Default")
      (node (ref "U1") (pin "27") (pinfunction "PB14_27") (pintype "passive+no_connect"))
    )
    (net (code "72") (name "unconnected-(U2-AIN1A-Pad29)") (class "Default")
      (node (ref "U2") (pin "29") (pinfunction "AIN1A_29") (pintype "passive+no_connect"))
    )
    (net (code "73") (name "unconnected-(U2-AIN1B-Pad30)") (class "Default")
      (node (ref "U2") (pin "30") (pinfunction "AIN1B_30") (pintype "passive+no_connect"))
    )
    (net (code "74") (name "unconnected-(U2-AIN2A-Pad25)") (class "Default")
      (node (ref "U2") (pin "25") (pinfunction "AIN2A_25") (pintype "passive+no_connect"))
    )
    (net (code "75") (name "unconnected-(U2-AIN2B-Pad26)") (class "Default")
      (node (ref "U2") (pin "26") (pinfunction "AIN2B_26") (pintype "passive+no_connect"))
    )
    (net (code "76") (name "unconnected-(U2-AIN3A-Pad23)") (class "Default")
      (node (ref "U2") (pin "23") (pinfunction "AIN3A_23") (pintype "passive+no_connect"))
    )
    (net (code "77") (name "unconnected-(U2-AIN3B-Pad24)") (class "Default")
      (node (ref "U2") (pin "24") (pinfunction "AIN3B_24") (pintype "passive+no_connect"))
    )
    (net (code "78") (name "unconnected-(U2-AIN4A-Pad21)") (class "Default")
      (node (ref "U2") (pin "21") (pinfunction "AIN4A_21") (pintype "passive+no_connect"))
    )
    (net (code "79") (name "unconnected-(U2-AIN4B-Pad22)") (class "Default")
      (node (ref "U2") (pin "22") (pinfunction "AIN4B_22") (pintype "passive+no_connect"))
    )
    (net (code "80") (name "unconnected-(U2-SPKR_OUTA+-Pad4)") (class "Default")
      (node (ref "U2") (pin "4") (pinfunction "SPKR_OUTA+_4") (pintype "passive+no_connect"))
    )
    (net (code "81") (name "unconnected-(U2-SPKR_OUTA–-Pad6)") (class "Default")
      (node (ref "U2") (pin "6") (pinfunction "SPKR_OUTA–_6") (pintype "passive+no_connect"))
    )
    (net (code "82") (name "unconnected-(U2-SPKR_OUTB+-Pad7)") (class "Default")
      (node (ref "U2") (pin "7") (pinfunction "SPKR_OUTB+_7") (pintype "passive+no_connect"))
    )
    (net (code "83") (name "unconnected-(U2-SPKR_OUTB–-Pad9)") (class "Default")
      (node (ref "U2") (pin "9") (pinfunction "SPKR_OUTB–_9") (pintype "passive+no_connect"))
    )
    (net (code "84") (name "unconnected-(U2-TSTO-Pad20)") (class "Default")
      (node (ref "U2") (pin "20") (pinfunction "TSTO_20") (pintype "passive+no_connect"))
    )
    (net (code "85") (name "unconnected-(U2-TSTO-Pad36)") (class "Default")
      (node (ref "U2") (pin "36") (pinfunction "TSTO_36") (pintype "passive+no_connect"))
    )
    (net (code "86") (name "unconnected-(U2-VP-Pad5)") (class "Default")
      (node (ref "U2") (pin "5") (pinfunction "VP_5") (pintype "passive+no_connect"))
    )
    (net (code "87") (name "unconnected-(U2-VP-Pad8)") (class "Default")
      (node (ref "U2") (pin "8") (pinfunction "VP_8") (pintype "passive+no_connect"))
    )
    (net (code "88") (name "unconnected-(U4-CHRG-Pad1)") (class "Default")
      (node (ref "U4") (pin "1") (pinfunction "CHRG_1") (pintype "passive+no_connect"))
    )
  )
)
